# Support.net
KiCad netlist of a schematic drawn in Altium Designer
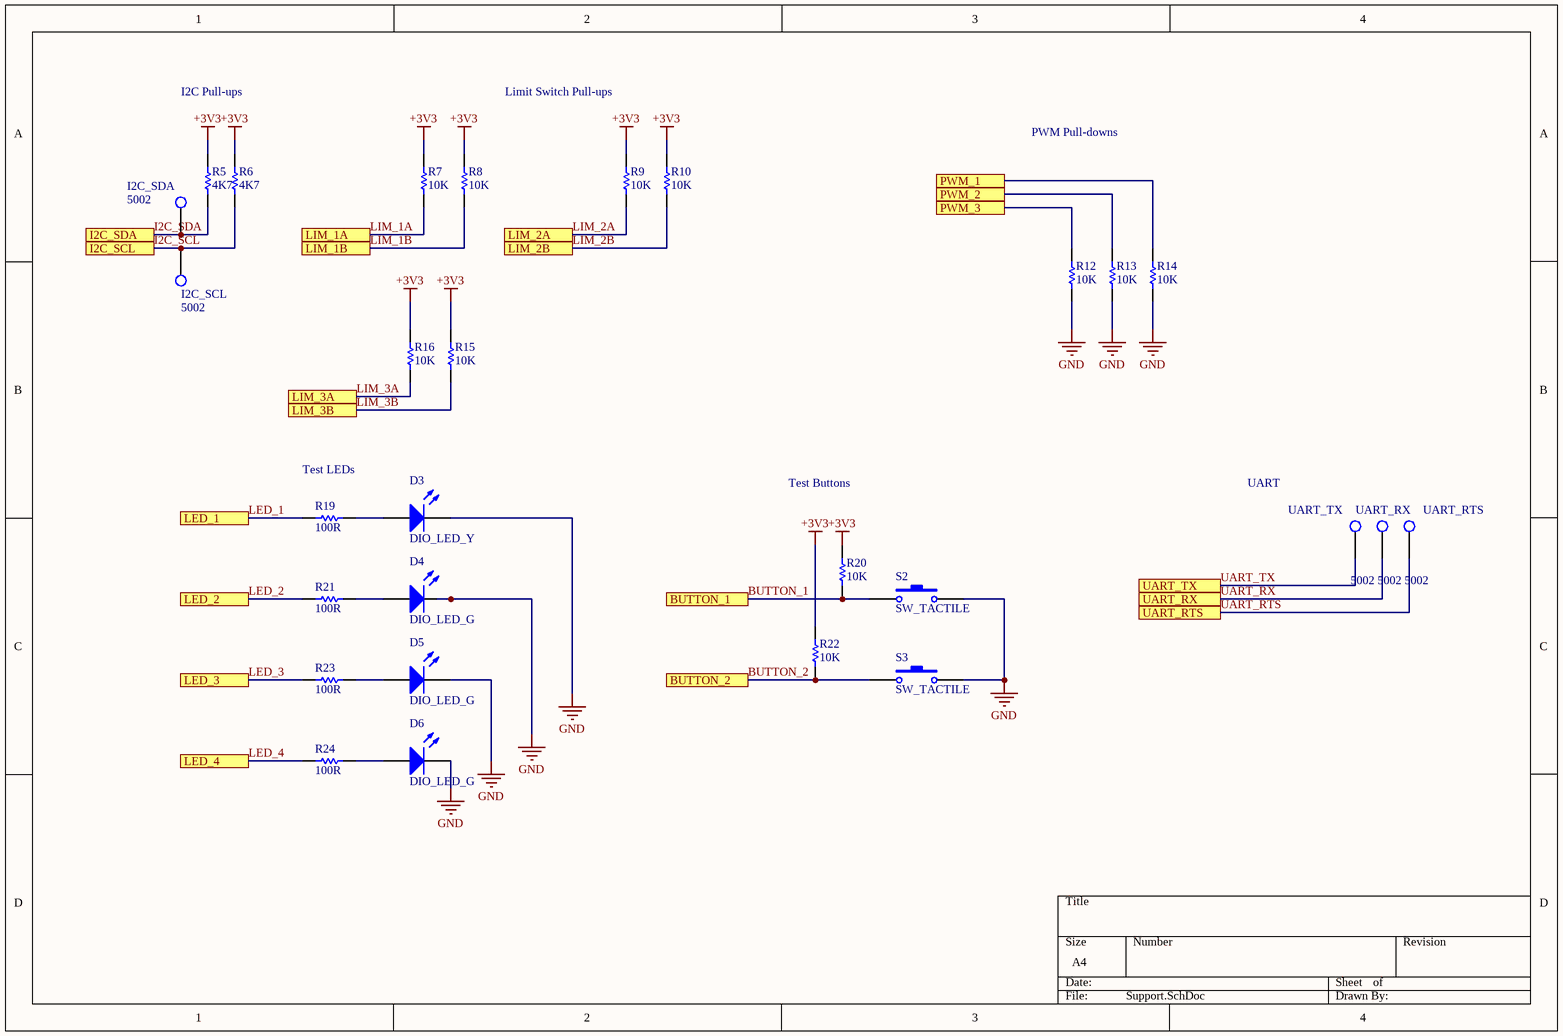
[diagram p0: Support.SchDoc]

(export (version "E")
  (design (tool "Eeschema 10.0.6"))
  (components
    (comp (ref "D3")
      (value "DIO_LED_Y")
      (footprint "LED_0805_LINE")
      (description "LED YELLOW DIFFUSED 0805 SMD")
      (fields (field (name "MANUFACTURER") "OSRAM") (field (name "MPN") "LY R976-PS-36"))
      (libsource (lib "UWRT_Schematic_Library_2019") (part "DIO_LED_Y"))
    )
    (comp (ref "D4")
      (value "DIO_LED_G")
      (footprint "LED_0805_LINE")
      (description "LED GREEN DIFFUSED 0805 SMD")
      (fields (field (name "MANUFACTURER") "OSRAM") (field (name "MPN") "LG R971-KN-1"))
      (libsource (lib "UWRT_Schematic_Library_2019") (part "DIO_LED_G"))
    )
    (comp (ref "D5")
      (value "DIO_LED_G")
      (footprint "LED_0805_LINE")
      (description "LED GREEN DIFFUSED 0805 SMD")
      (fields (field (name "MANUFACTURER") "OSRAM") (field (name "MPN") "LG R971-KN-1"))
      (libsource (lib "UWRT_Schematic_Library_2019") (part "DIO_LED_G"))
    )
    (comp (ref "D6")
      (value "DIO_LED_G")
      (footprint "LED_0805_LINE")
      (description "LED GREEN DIFFUSED 0805 SMD")
      (fields (field (name "MANUFACTURER") "OSRAM") (field (name "MPN") "LG R971-KN-1"))
      (libsource (lib "UWRT_Schematic_Library_2019") (part "DIO_LED_G"))
    )
    (comp (ref "R5")
      (value "4K7")
      (footprint "RESC0603(1608)_N")
      (description "RES SMD 4.7K OHM 5% 1/10W 0603")
      (fields (field (name "MANUFACTURER") "Yageo") (field (name "TOLERANCE") "5%"))
      (libsource (lib "UWRT_Schematic_Library_2019") (part "RES_4K7_0603"))
    )
    (comp (ref "R6")
      (value "4K7")
      (footprint "RESC0603(1608)_N")
      (description "RES SMD 4.7K OHM 5% 1/10W 0603")
      (fields (field (name "MANUFACTURER") "Yageo") (field (name "TOLERANCE") "5%"))
      (libsource (lib "UWRT_Schematic_Library_2019") (part "RES_4K7_0603"))
    )
    (comp (ref "R7")
      (value "10K")
      (footprint "RESC0603(1608)_N")
      (description "RES SMD 10K OHM 5% 1/10W 0603")
      (fields (field (name "MANUFACTURER") "Yageo") (field (name "TOLERANCE") "5%"))
      (libsource (lib "UWRT_Schematic_Library_2019") (part "RES_10K_0603"))
    )
    (comp (ref "R8")
      (value "10K")
      (footprint "RESC0603(1608)_N")
      (description "RES SMD 10K OHM 5% 1/10W 0603")
      (fields (field (name "MANUFACTURER") "Yageo") (field (name "TOLERANCE") "5%"))
      (libsource (lib "UWRT_Schematic_Library_2019") (part "RES_10K_0603"))
    )
    (comp (ref "R9")
      (value "10K")
      (footprint "RESC0603(1608)_N")
      (description "RES SMD 10K OHM 5% 1/10W 0603")
      (fields (field (name "MANUFACTURER") "Yageo") (field (name "TOLERANCE") "5%"))
      (libsource (lib "UWRT_Schematic_Library_2019") (part "RES_10K_0603"))
    )
    (comp (ref "R10")
      (value "10K")
      (footprint "RESC0603(1608)_N")
      (description "RES SMD 10K OHM 5% 1/10W 0603")
      (fields (field (name "MANUFACTURER") "Yageo") (field (name "TOLERANCE") "5%"))
      (libsource (lib "UWRT_Schematic_Library_2019") (part "RES_10K_0603"))
    )
    (comp (ref "R12")
      (value "10K")
      (footprint "RESC0603(1608)_N")
      (description "RES SMD 10K OHM 5% 1/10W 0603")
      (fields (field (name "MANUFACTURER") "Yageo") (field (name "TOLERANCE") "5%"))
      (libsource (lib "UWRT_Schematic_Library_2019") (part "RES_10K_0603"))
    )
    (comp (ref "R13")
      (value "10K")
      (footprint "RESC0603(1608)_N")
      (description "RES SMD 10K OHM 5% 1/10W 0603")
      (fields (field (name "MANUFACTURER") "Yageo") (field (name "TOLERANCE") "5%"))
      (libsource (lib "UWRT_Schematic_Library_2019") (part "RES_10K_0603"))
    )
    (comp (ref "R14")
      (value "10K")
      (footprint "RESC0603(1608)_N")
      (description "RES SMD 10K OHM 5% 1/10W 0603")
      (fields (field (name "MANUFACTURER") "Yageo") (field (name "TOLERANCE") "5%"))
      (libsource (lib "UWRT_Schematic_Library_2019") (part "RES_10K_0603"))
    )
    (comp (ref "R15")
      (value "10K")
      (footprint "RESC0603(1608)_N")
      (description "RES SMD 10K OHM 5% 1/10W 0603")
      (fields (field (name "MANUFACTURER") "Yageo") (field (name "TOLERANCE") "5%"))
      (libsource (lib "UWRT_Schematic_Library_2019") (part "RES_10K_0603"))
    )
    (comp (ref "R16")
      (value "10K")
      (footprint "RESC0603(1608)_N")
      (description "RES SMD 10K OHM 5% 1/10W 0603")
      (fields (field (name "MANUFACTURER") "Yageo") (field (name "TOLERANCE") "5%"))
      (libsource (lib "UWRT_Schematic_Library_2019") (part "RES_10K_0603"))
    )
    (comp (ref "R19")
      (value "100R")
      (footprint "RESC0603(1608)_N")
      (description "RES SMD 100 OHM 1% 1/10W 0603")
      (fields (field (name "MANUFACTURER") "Yageo") (field (name "TOLERANCE") "1%"))
      (libsource (lib "UWRT_Schematic_Library_2019") (part "RES_100R_0603"))
    )
    (comp (ref "R20")
      (value "10K")
      (footprint "RESC0603(1608)_N")
      (description "RES SMD 10K OHM 5% 1/10W 0603")
      (fields (field (name "MANUFACTURER") "Yageo") (field (name "TOLERANCE") "5%"))
      (libsource (lib "UWRT_Schematic_Library_2019") (part "RES_10K_0603"))
    )
    (comp (ref "R21")
      (value "100R")
      (footprint "RESC0603(1608)_N")
      (description "RES SMD 100 OHM 1% 1/10W 0603")
      (fields (field (name "MANUFACTURER") "Yageo") (field (name "TOLERANCE") "1%"))
      (libsource (lib "UWRT_Schematic_Library_2019") (part "RES_100R_0603"))
    )
    (comp (ref "R22")
      (value "10K")
      (footprint "RESC0603(1608)_N")
      (description "RES SMD 10K OHM 5% 1/10W 0603")
      (fields (field (name "MANUFACTURER") "Yageo") (field (name "TOLERANCE") "5%"))
      (libsource (lib "UWRT_Schematic_Library_2019") (part "RES_10K_0603"))
    )
    (comp (ref "R23")
      (value "100R")
      (footprint "RESC0603(1608)_N")
      (description "RES SMD 100 OHM 1% 1/10W 0603")
      (fields (field (name "MANUFACTURER") "Yageo") (field (name "TOLERANCE") "1%"))
      (libsource (lib "UWRT_Schematic_Library_2019") (part "RES_100R_0603"))
    )
    (comp (ref "R24")
      (value "100R")
      (footprint "RESC0603(1608)_N")
      (description "RES SMD 100 OHM 1% 1/10W 0603")
      (fields (field (name "MANUFACTURER") "Yageo") (field (name "TOLERANCE") "1%"))
      (libsource (lib "UWRT_Schematic_Library_2019") (part "RES_100R_0603"))
    )
    (comp (ref "S2")
      (value "SW_TACTILE")
      (footprint "B3U-1100P")
      (description "Tactile Switch (Grey)")
      (fields (field (name "DIGIKEY PART NUMBER") "SW1021TR-ND") (field (name "MPN") "B3U-1100P"))
      (libsource (lib "UWRT_Schematic_Library_2019") (part "SW_TACTILE"))
    )
    (comp (ref "S3")
      (value "SW_TACTILE")
      (footprint "B3U-1100P")
      (description "Tactile Switch (Grey)")
      (fields (field (name "DIGIKEY PART NUMBER") "SW1021TR-ND") (field (name "MPN") "B3U-1100P"))
      (libsource (lib "UWRT_Schematic_Library_2019") (part "SW_TACTILE"))
    )
    (comp (ref "TP6")
      (value "I2C_SDA")
      (footprint "TESTPOINT_LOOP")
      (description "PC TEST POINT MINIATURE WHITE")
      (fields
        (field (name "DIGIKEY PART NUMBER") "36-5002-ND")
        (field (name "MANUFACTURER") "Keystone Electronics")
        (field (name "MPN") "5002")
      )
      (libsource (lib "UWRT_Schematic_Library_2019") (part "TESTPOINT_LOOP"))
    )
    (comp (ref "TP7")
      (value "I2C_SCL")
      (footprint "TESTPOINT_LOOP")
      (description "PC TEST POINT MINIATURE WHITE")
      (fields
        (field (name "DIGIKEY PART NUMBER") "36-5002-ND")
        (field (name "MANUFACTURER") "Keystone Electronics")
        (field (name "MPN") "5002")
      )
      (libsource (lib "UWRT_Schematic_Library_2019") (part "TESTPOINT_LOOP"))
    )
    (comp (ref "TP8")
      (value "UART_TX")
      (footprint "TESTPOINT_LOOP")
      (description "PC TEST POINT MINIATURE WHITE")
      (fields
        (field (name "DIGIKEY PART NUMBER") "36-5002-ND")
        (field (name "MANUFACTURER") "Keystone Electronics")
        (field (name "MPN") "5002")
      )
      (libsource (lib "UWRT_Schematic_Library_2019") (part "TESTPOINT_LOOP"))
    )
    (comp (ref "TP9")
      (value "UART_RX")
      (footprint "TESTPOINT_LOOP")
      (description "PC TEST POINT MINIATURE WHITE")
      (fields
        (field (name "DIGIKEY PART NUMBER") "36-5002-ND")
        (field (name "MANUFACTURER") "Keystone Electronics")
        (field (name "MPN") "5002")
      )
      (libsource (lib "UWRT_Schematic_Library_2019") (part "TESTPOINT_LOOP"))
    )
    (comp (ref "TP10")
      (value "UART_RTS")
      (footprint "TESTPOINT_LOOP")
      (description "PC TEST POINT MINIATURE WHITE")
      (fields
        (field (name "DIGIKEY PART NUMBER") "36-5002-ND")
        (field (name "MANUFACTURER") "Keystone Electronics")
        (field (name "MPN") "5002")
      )
      (libsource (lib "UWRT_Schematic_Library_2019") (part "TESTPOINT_LOOP"))
    )
  )
  (nets
    (net (code "1") (name "+3V3") (class "Default")
      (node (ref "R10") (pin "2") (pinfunction "2_2") (pintype "passive"))
      (node (ref "R15") (pin "2") (pinfunction "2_2") (pintype "passive"))
      (node (ref "R16") (pin "2") (pinfunction "2_2") (pintype "passive"))
      (node (ref "R20") (pin "2") (pinfunction "2_2") (pintype "passive"))
      (node (ref "R22") (pin "1") (pinfunction "1_1") (pintype "passive"))
      (node (ref "R5") (pin "2") (pinfunction "2_2") (pintype "passive"))
      (node (ref "R6") (pin "2") (pinfunction "2_2") (pintype "passive"))
      (node (ref "R7") (pin "2") (pinfunction "2_2") (pintype "passive"))
      (node (ref "R8") (pin "2") (pinfunction "2_2") (pintype "passive"))
      (node (ref "R9") (pin "2") (pinfunction "2_2") (pintype "passive"))
    )
    (net (code "2") (name "/BUTTON_1") (class "Default")
      (node (ref "R20") (pin "1") (pinfunction "1_1") (pintype "passive"))
      (node (ref "S2") (pin "1") (pinfunction "1_1") (pintype "passive"))
    )
    (net (code "3") (name "/BUTTON_2") (class "Default")
      (node (ref "R22") (pin "2") (pinfunction "2_2") (pintype "passive"))
      (node (ref "S3") (pin "1") (pinfunction "1_1") (pintype "passive"))
    )
    (net (code "4") (name "/I2C_SCL") (class "Default")
      (node (ref "R6") (pin "1") (pinfunction "1_1") (pintype "passive"))
      (node (ref "TP7") (pin "1") (pinfunction "=value_1") (pintype "passive"))
    )
    (net (code "5") (name "/I2C_SDA") (class "Default")
      (node (ref "R5") (pin "1") (pinfunction "1_1") (pintype "passive"))
      (node (ref "TP6") (pin "1") (pinfunction "=value_1") (pintype "passive"))
    )
    (net (code "6") (name "/LED_1") (class "Default")
      (node (ref "R19") (pin "1") (pinfunction "1_1") (pintype "passive"))
    )
    (net (code "7") (name "/LED_2") (class "Default")
      (node (ref "R21") (pin "1") (pinfunction "1_1") (pintype "passive"))
    )
    (net (code "8") (name "/LED_3") (class "Default")
      (node (ref "R23") (pin "1") (pinfunction "1_1") (pintype "passive"))
    )
    (net (code "9") (name "/LED_4") (class "Default")
      (node (ref "R24") (pin "1") (pinfunction "1_1") (pintype "passive"))
    )
    (net (code "10") (name "/LIM_1A") (class "Default")
      (node (ref "R7") (pin "1") (pinfunction "1_1") (pintype "passive"))
    )
    (net (code "11") (name "/LIM_1B") (class "Default")
      (node (ref "R8") (pin "1") (pinfunction "1_1") (pintype "passive"))
    )
    (net (code "12") (name "/LIM_2A") (class "Default")
      (node (ref "R9") (pin "1") (pinfunction "1_1") (pintype "passive"))
    )
    (net (code "13") (name "/LIM_2B") (class "Default")
      (node (ref "R10") (pin "1") (pinfunction "1_1") (pintype "passive"))
    )
    (net (code "14") (name "/LIM_3A") (class "Default")
      (node (ref "R16") (pin "1") (pinfunction "1_1") (pintype "passive"))
    )
    (net (code "15") (name "/LIM_3B") (class "Default")
      (node (ref "R15") (pin "1") (pinfunction "1_1") (pintype "passive"))
    )
    (net (code "16") (name "/PWM_1") (class "Default")
      (node (ref "R14") (pin "2") (pinfunction "2_2") (pintype "passive"))
    )
    (net (code "17") (name "/PWM_2") (class "Default")
      (node (ref "R13") (pin "2") (pinfunction "2_2") (pintype "passive"))
    )
    (net (code "18") (name "/PWM_3") (class "Default")
      (node (ref "R12") (pin "2") (pinfunction "2_2") (pintype "passive"))
    )
    (net (code "19") (name "/UART_RTS") (class "Default")
      (node (ref "TP10") (pin "1") (pinfunction "=value_1") (pintype "passive"))
    )
    (net (code "20") (name "/UART_RX") (class "Default")
      (node (ref "TP9") (pin "1") (pinfunction "=value_1") (pintype "passive"))
    )
    (net (code "21") (name "/UART_TX") (class "Default")
      (node (ref "TP8") (pin "1") (pinfunction "=value_1") (pintype "passive"))
    )
    (net (code "22") (name "GND") (class "Default")
      (node (ref "D3") (pin "2") (pinfunction "K_2") (pintype "passive"))
      (node (ref "D4") (pin "2") (pinfunction "K_2") (pintype "passive"))
      (node (ref "D5") (pin "2") (pinfunction "K_2") (pintype "passive"))
      (node (ref "D6") (pin "2") (pinfunction "K_2") (pintype "passive"))
      (node (ref "R12") (pin "1") (pinfunction "1_1") (pintype "passive"))
      (node (ref "R13") (pin "1") (pinfunction "1_1") (pintype "passive"))
      (node (ref "R14") (pin "1") (pinfunction "1_1") (pintype "passive"))
      (node (ref "S2") (pin "2") (pinfunction "2_2") (pintype "passive"))
      (node (ref "S3") (pin "2") (pinfunction "2_2") (pintype "passive"))
    )
    (net (code "23") (name "Net-(D3-A)") (class "Default")
      (node (ref "D3") (pin "1") (pinfunction "A_1") (pintype "passive"))
      (node (ref "R19") (pin "2") (pinfunction "2_2") (pintype "passive"))
    )
    (net (code "24") (name "Net-(D4-A)") (class "Default")
      (node (ref "D4") (pin "1") (pinfunction "A_1") (pintype "passive"))
      (node (ref "R21") (pin "2") (pinfunction "2_2") (pintype "passive"))
    )
    (net (code "25") (name "Net-(D5-A)") (class "Default")
      (node (ref "D5") (pin "1") (pinfunction "A_1") (pintype "passive"))
      (node (ref "R23") (pin "2") (pinfunction "2_2") (pintype "passive"))
    )
    (net (code "26") (name "Net-(D6-A)") (class "Default")
      (node (ref "D6") (pin "1") (pinfunction "A_1") (pintype "passive"))
      (node (ref "R24") (pin "2") (pinfunction "2_2") (pintype "passive"))
    )
  )
)
